# CAMERA_DVP_FPC24_OV7670.net
KiCad netlist of a schematic drawn in Altium Designer
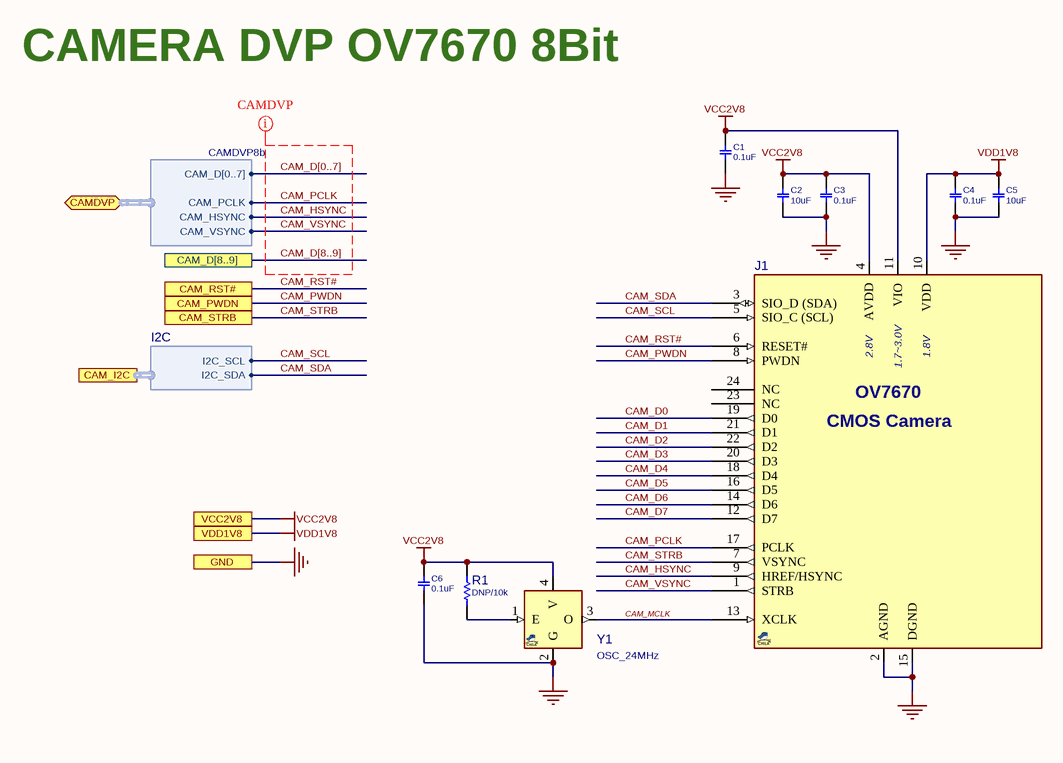
[diagram p0: CAMERA_DVP_FPC24_OV7670.SchDoc]

(export (version "E")
  (design (tool "Eeschema 10.0.6"))
  (components
    (comp (ref "C1")
      (value "0.1uF")
      (footprint "C0402")
      (description "CAP, MLCC")
      (libsource (lib "mlcc_smd_passive") (part "CAP_SMD_MLCC_100n50TDK"))
    )
    (comp (ref "C2")
      (value "10uF")
      (footprint "C0402")
      (description "CAP, MLCC")
      (libsource (lib "mlcc_smd_passive") (part "CAP_SMD_MLCC_100n50TDK"))
    )
    (comp (ref "C3")
      (value "0.1uF")
      (footprint "C0402")
      (description "CAP, MLCC")
      (libsource (lib "mlcc_smd_passive") (part "CAP_SMD_MLCC_100n50TDK"))
    )
    (comp (ref "C4")
      (value "0.1uF")
      (footprint "C0402")
      (description "CAP, MLCC")
      (libsource (lib "mlcc_smd_passive") (part "CAP_SMD_MLCC_100n50TDK"))
    )
    (comp (ref "C5")
      (value "10uF")
      (footprint "C0402")
      (description "CAP, MLCC")
      (libsource (lib "mlcc_smd_passive") (part "CAP_SMD_MLCC_100n50TDK"))
    )
    (comp (ref "C6")
      (value "0.1uF")
      (footprint "C0402")
      (description "CAP, MLCC")
      (libsource (lib "mlcc_smd_passive") (part "CAP_SMD_MLCC_100n50TDK"))
    )
    (comp (ref "J1")
      (value "OV7670")
      (footprint "FPC50_24")
      (description "Camera Module, Color CMOS VGA (640 x 480)  DVP FPC24")
      (libsource (lib "camera") (part "OV7670_FPC24"))
    )
    (comp (ref "R1")
      (value "DNP/10k")
      (footprint "R0402")
      (description "RESISTOR, SMD, THICK FILM, YAGEO")
      (fields (field (name "MANF_P#") "RC0402FR-071KL") (field (name "MANF") "Yageo"))
      (libsource (lib "res_smd_Yageo0402_thickfilm") (part "RES_SMD_1K_0402YK"))
    )
    (comp (ref "Y1")
      (value "OSC_24MHz")
      (footprint "XTL_4_3225GEN")
      (description "CLOCK OSCILLATOR, 25MHz, 10PPM, 3.2X2.5mm")
      (fields (field (name "MANF") "ECS") (field (name "MANF_P#") "OT322524MJBA4SL"))
      (libsource (lib "crystal_osc") (part "OSC_4_25MHz_3225E"))
    )
  )
  (nets
    (net (code "5") (name "/CAM_D0") (class "Default")
      (node (ref "J1") (pin "19") (pinfunction "D0_19") (pintype "output"))
    )
    (net (code "6") (name "/CAM_D1") (class "Default")
      (node (ref "J1") (pin "21") (pinfunction "D1_21") (pintype "output"))
    )
    (net (code "7") (name "/CAM_D2") (class "Default")
      (node (ref "J1") (pin "22") (pinfunction "D2_22") (pintype "output"))
    )
    (net (code "8") (name "/CAM_D3") (class "Default")
      (node (ref "J1") (pin "20") (pinfunction "D3_20") (pintype "output"))
    )
    (net (code "9") (name "/CAM_D4") (class "Default")
      (node (ref "J1") (pin "18") (pinfunction "D4_18") (pintype "output"))
    )
    (net (code "10") (name "/CAM_D5") (class "Default")
      (node (ref "J1") (pin "16") (pinfunction "D5_16") (pintype "output"))
    )
    (net (code "11") (name "/CAM_D6") (class "Default")
      (node (ref "J1") (pin "14") (pinfunction "D6_14") (pintype "output"))
    )
    (net (code "12") (name "/CAM_D7") (class "Default")
      (node (ref "J1") (pin "12") (pinfunction "D7_12") (pintype "output"))
    )
    (net (code "15") (name "/CAM_HSYNC") (class "Default")
      (node (ref "J1") (pin "9") (pinfunction "HREF/HSYNC_9") (pintype "output"))
    )
    (net (code "16") (name "/CAM_MCLK") (class "Default")
      (node (ref "J1") (pin "13") (pinfunction "XCLK_13") (pintype "input"))
      (node (ref "Y1") (pin "3") (pinfunction "O_3") (pintype "output"))
    )
    (net (code "17") (name "/CAM_PCLK") (class "Default")
      (node (ref "J1") (pin "17") (pinfunction "PCLK_17") (pintype "output"))
    )
    (net (code "18") (name "/CAM_PWDN") (class "Default")
      (node (ref "J1") (pin "8") (pinfunction "PWDN_8") (pintype "input"))
    )
    (net (code "19") (name "/CAM_RST#") (class "Default")
      (node (ref "J1") (pin "6") (pinfunction "RESET#_6") (pintype "input"))
    )
    (net (code "20") (name "/CAM_SCL") (class "Default")
      (node (ref "J1") (pin "5") (pinfunction "SIO_C_(SCL)_5") (pintype "input"))
    )
    (net (code "21") (name "/CAM_SDA") (class "Default")
      (node (ref "J1") (pin "3") (pinfunction "SIO_D_(SDA)_3") (pintype "bidirectional"))
    )
    (net (code "22") (name "/CAM_STRB") (class "Default")
      (node (ref "J1") (pin "7") (pinfunction "VSYNC_7") (pintype "output"))
    )
    (net (code "23") (name "/CAM_VSYNC") (class "Default")
      (node (ref "J1") (pin "1") (pinfunction "STRB_1") (pintype "output"))
    )
    (net (code "26") (name "GND") (class "Default")
      (node (ref "C1") (pin "2") (pinfunction "2_2") (pintype "passive"))
      (node (ref "C2") (pin "2") (pinfunction "2_2") (pintype "passive"))
      (node (ref "C3") (pin "2") (pinfunction "2_2") (pintype "passive"))
      (node (ref "C4") (pin "2") (pinfunction "2_2") (pintype "passive"))
      (node (ref "C5") (pin "2") (pinfunction "2_2") (pintype "passive"))
      (node (ref "C6") (pin "2") (pinfunction "2_2") (pintype "passive"))
      (node (ref "J1") (pin "15") (pinfunction "DGND_15") (pintype "power_in"))
      (node (ref "J1") (pin "2") (pinfunction "AGND_2") (pintype "power_in"))
      (node (ref "Y1") (pin "2") (pinfunction "G_2") (pintype "power_in"))
    )
    (net (code "27") (name "Net-(Y1-E)") (class "Default")
      (node (ref "R1") (pin "2") (pinfunction "2_2") (pintype "passive"))
      (node (ref "Y1") (pin "1") (pinfunction "E_1") (pintype "input"))
    )
    (net (code "28") (name "VCC2V8") (class "Default")
      (node (ref "C1") (pin "1") (pinfunction "1_1") (pintype "passive"))
      (node (ref "C2") (pin "1") (pinfunction "1_1") (pintype "passive"))
      (node (ref "C3") (pin "1") (pinfunction "1_1") (pintype "passive"))
      (node (ref "C6") (pin "1") (pinfunction "1_1") (pintype "passive"))
      (node (ref "J1") (pin "11") (pinfunction "VIO_11") (pintype "power_in"))
      (node (ref "J1") (pin "4") (pinfunction "AVDD_4") (pintype "power_in"))
      (node (ref "R1") (pin "1") (pinfunction "1_1") (pintype "passive"))
      (node (ref "Y1") (pin "4") (pinfunction "V_4") (pintype "power_in"))
    )
    (net (code "29") (name "VDD1V8") (class "Default")
      (node (ref "C4") (pin "1") (pinfunction "1_1") (pintype "passive"))
      (node (ref "C5") (pin "1") (pinfunction "1_1") (pintype "passive"))
      (node (ref "J1") (pin "10") (pinfunction "VDD_10") (pintype "power_in"))
    )
    (net (code "30") (name "unconnected-(J1-NC-Pad23)") (class "Default")
      (node (ref "J1") (pin "23") (pinfunction "NC_23") (pintype "passive"))
    )
    (net (code "31") (name "unconnected-(J1-NC-Pad24)") (class "Default")
      (node (ref "J1") (pin "24") (pinfunction "NC_24") (pintype "passive"))
    )
  )
)
